# Shield_Engino.net
KiCad netlist of a schematic drawn in EAGLE
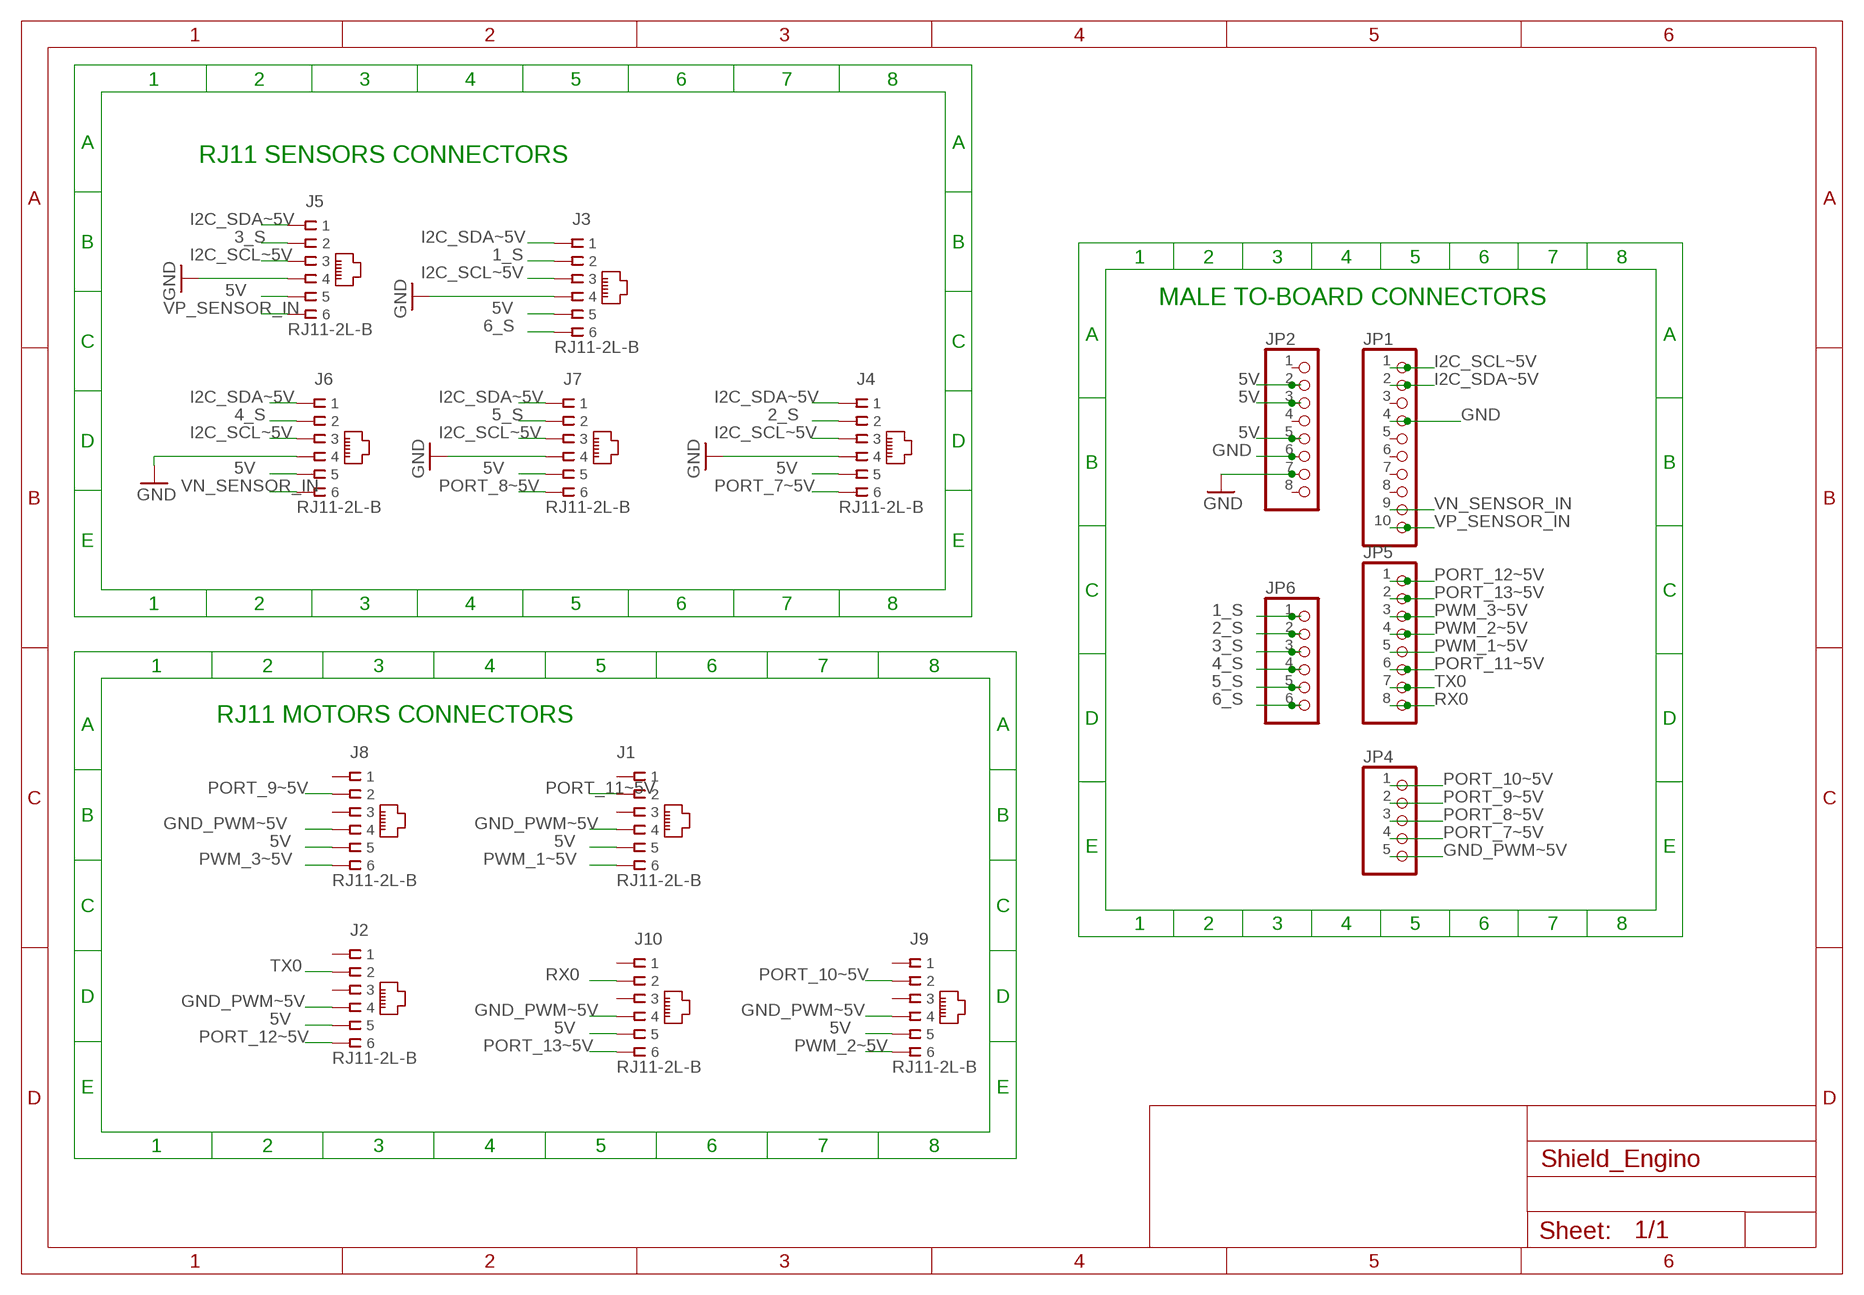
[diagram p0: schematic, sheet 1]

(export (version "E")
  (design (tool "Eeschema 10.0.6"))
  (components
    (comp (ref "J1")
      (value "RJ11-2L-B")
      (footprint "eagle-import:RJ11-NO_SHIELD")
      (fields (field (name "MF") "TYCO ELECTRONICS"))
      (libsource (lib "eagle-import") (part "RJ11-2L-B"))
    )
    (comp (ref "J2")
      (value "RJ11-2L-B")
      (footprint "eagle-import:RJ11-NO_SHIELD")
      (fields (field (name "MF") "TYCO ELECTRONICS"))
      (libsource (lib "eagle-import") (part "RJ11-2L-B"))
    )
    (comp (ref "J3")
      (value "RJ11-2L-B")
      (footprint "eagle-import:RJ11-NO_SHIELD")
      (fields (field (name "MF") "TYCO ELECTRONICS"))
      (libsource (lib "eagle-import") (part "RJ11-2L-B"))
    )
    (comp (ref "J4")
      (value "RJ11-2L-B")
      (footprint "eagle-import:RJ11-NO_SHIELD")
      (fields (field (name "MF") "TYCO ELECTRONICS"))
      (libsource (lib "eagle-import") (part "RJ11-2L-B"))
    )
    (comp (ref "J5")
      (value "RJ11-2L-B")
      (footprint "eagle-import:RJ11-NO_SHIELD")
      (fields (field (name "MF") "TYCO ELECTRONICS"))
      (libsource (lib "eagle-import") (part "RJ11-2L-B"))
    )
    (comp (ref "J6")
      (value "RJ11-2L-B")
      (footprint "eagle-import:RJ11-NO_SHIELD")
      (fields (field (name "MF") "TYCO ELECTRONICS"))
      (libsource (lib "eagle-import") (part "RJ11-2L-B"))
    )
    (comp (ref "J7")
      (value "RJ11-2L-B")
      (footprint "eagle-import:RJ11-NO_SHIELD")
      (fields (field (name "MF") "TYCO ELECTRONICS"))
      (libsource (lib "eagle-import") (part "RJ11-2L-B"))
    )
    (comp (ref "J8")
      (value "RJ11-2L-B")
      (footprint "eagle-import:RJ11-NO_SHIELD")
      (fields (field (name "MF") "TYCO ELECTRONICS"))
      (libsource (lib "eagle-import") (part "RJ11-2L-B"))
    )
    (comp (ref "J9")
      (value "RJ11-2L-B")
      (footprint "eagle-import:RJ11-NO_SHIELD")
      (fields (field (name "MF") "TYCO ELECTRONICS"))
      (libsource (lib "eagle-import") (part "RJ11-2L-B"))
    )
    (comp (ref "J10")
      (value "RJ11-2L-B")
      (footprint "eagle-import:RJ11-NO_SHIELD")
      (fields (field (name "MF") "TYCO ELECTRONICS"))
      (libsource (lib "eagle-import") (part "RJ11-2L-B"))
    )
    (comp (ref "JP1")
      (value "PINHD-1X10_2.54-SMD")
      (footprint "eagle-import:1X10SMD")
      (libsource (lib "eagle-import") (part "PINHD-1X10_2.54-SMD"))
    )
    (comp (ref "JP2")
      (value "PINHD-1X8_2.54-SMD")
      (footprint "eagle-import:1X08SMD")
      (libsource (lib "eagle-import") (part "PINHD-1X8_2.54-SMD"))
    )
    (comp (ref "JP4")
      (value "PINHD-1X5_2.54-SMD")
      (footprint "eagle-import:1X05SMD")
      (libsource (lib "eagle-import") (part "PINHD-1X5_2.54-SMD"))
    )
    (comp (ref "JP5")
      (value "PINHD-1X8_2.54-SMD")
      (footprint "eagle-import:1X08SMD")
      (libsource (lib "eagle-import") (part "PINHD-1X8_2.54-SMD"))
    )
    (comp (ref "JP6")
      (value "PINHD-1X6_2.54-SMD")
      (footprint "eagle-import:1X06SMD")
      (libsource (lib "eagle-import") (part "PINHD-1X6_2.54-SMD"))
    )
  )
  (nets
    (net (code "1") (name "/1_S") (class "Default")
      (node (ref "J3") (pin "2") (pinfunction "2_2") (pintype "passive"))
      (node (ref "JP6") (pin "1") (pinfunction "1_1") (pintype "passive"))
    )
    (net (code "2") (name "/2_S") (class "Default")
      (node (ref "J4") (pin "2") (pinfunction "2_2") (pintype "passive"))
      (node (ref "JP6") (pin "2") (pinfunction "2_2") (pintype "passive"))
    )
    (net (code "3") (name "/3_S") (class "Default")
      (node (ref "J5") (pin "2") (pinfunction "2_2") (pintype "passive"))
      (node (ref "JP6") (pin "3") (pinfunction "3_3") (pintype "passive"))
    )
    (net (code "4") (name "/4_S") (class "Default")
      (node (ref "J6") (pin "2") (pinfunction "2_2") (pintype "passive"))
      (node (ref "JP6") (pin "4") (pinfunction "4_4") (pintype "passive"))
    )
    (net (code "5") (name "/5V") (class "Default")
      (node (ref "J1") (pin "5") (pinfunction "5_5") (pintype "passive"))
      (node (ref "J10") (pin "5") (pinfunction "5_5") (pintype "passive"))
      (node (ref "J2") (pin "5") (pinfunction "5_5") (pintype "passive"))
      (node (ref "J3") (pin "5") (pinfunction "5_5") (pintype "passive"))
      (node (ref "J4") (pin "5") (pinfunction "5_5") (pintype "passive"))
      (node (ref "J5") (pin "5") (pinfunction "5_5") (pintype "passive"))
      (node (ref "J6") (pin "5") (pinfunction "5_5") (pintype "passive"))
      (node (ref "J7") (pin "5") (pinfunction "5_5") (pintype "passive"))
      (node (ref "J8") (pin "5") (pinfunction "5_5") (pintype "passive"))
      (node (ref "J9") (pin "5") (pinfunction "5_5") (pintype "passive"))
      (node (ref "JP2") (pin "2") (pinfunction "2_2") (pintype "passive"))
      (node (ref "JP2") (pin "3") (pinfunction "3_3") (pintype "passive"))
      (node (ref "JP2") (pin "5") (pinfunction "5_5") (pintype "passive"))
    )
    (net (code "6") (name "/5_S") (class "Default")
      (node (ref "J7") (pin "2") (pinfunction "2_2") (pintype "passive"))
      (node (ref "JP6") (pin "5") (pinfunction "5_5") (pintype "passive"))
    )
    (net (code "7") (name "/6_S") (class "Default")
      (node (ref "J3") (pin "6") (pinfunction "6_6") (pintype "passive"))
      (node (ref "JP6") (pin "6") (pinfunction "6_6") (pintype "passive"))
    )
    (net (code "8") (name "/GND_PWM~{5V}") (class "Default")
      (node (ref "J1") (pin "4") (pinfunction "4_4") (pintype "passive"))
      (node (ref "J10") (pin "4") (pinfunction "4_4") (pintype "passive"))
      (node (ref "J2") (pin "4") (pinfunction "4_4") (pintype "passive"))
      (node (ref "J8") (pin "4") (pinfunction "4_4") (pintype "passive"))
      (node (ref "J9") (pin "4") (pinfunction "4_4") (pintype "passive"))
      (node (ref "JP4") (pin "5") (pinfunction "5_5") (pintype "passive"))
    )
    (net (code "9") (name "/I2C_SCL~{5V}") (class "Default")
      (node (ref "J3") (pin "3") (pinfunction "3_3") (pintype "passive"))
      (node (ref "J4") (pin "3") (pinfunction "3_3") (pintype "passive"))
      (node (ref "J5") (pin "3") (pinfunction "3_3") (pintype "passive"))
      (node (ref "J6") (pin "3") (pinfunction "3_3") (pintype "passive"))
      (node (ref "J7") (pin "3") (pinfunction "3_3") (pintype "passive"))
      (node (ref "JP1") (pin "1") (pinfunction "1_1") (pintype "passive"))
    )
    (net (code "10") (name "/I2C_SDA~{5V}") (class "Default")
      (node (ref "J3") (pin "1") (pinfunction "1_1") (pintype "passive"))
      (node (ref "J4") (pin "1") (pinfunction "1_1") (pintype "passive"))
      (node (ref "J5") (pin "1") (pinfunction "1_1") (pintype "passive"))
      (node (ref "J6") (pin "1") (pinfunction "1_1") (pintype "passive"))
      (node (ref "J7") (pin "1") (pinfunction "1_1") (pintype "passive"))
      (node (ref "JP1") (pin "2") (pinfunction "2_2") (pintype "passive"))
    )
    (net (code "11") (name "/PORT_7~{5V}") (class "Default")
      (node (ref "J4") (pin "6") (pinfunction "6_6") (pintype "passive"))
      (node (ref "JP4") (pin "4") (pinfunction "4_4") (pintype "passive"))
    )
    (net (code "12") (name "/PORT_8~{5V}") (class "Default")
      (node (ref "J7") (pin "6") (pinfunction "6_6") (pintype "passive"))
      (node (ref "JP4") (pin "3") (pinfunction "3_3") (pintype "passive"))
    )
    (net (code "13") (name "/PORT_9~{5V}") (class "Default")
      (node (ref "J8") (pin "2") (pinfunction "2_2") (pintype "passive"))
      (node (ref "JP4") (pin "2") (pinfunction "2_2") (pintype "passive"))
    )
    (net (code "14") (name "/PORT_10~{5V}") (class "Default")
      (node (ref "J9") (pin "2") (pinfunction "2_2") (pintype "passive"))
      (node (ref "JP4") (pin "1") (pinfunction "1_1") (pintype "passive"))
    )
    (net (code "15") (name "/PORT_11~{5V}") (class "Default")
      (node (ref "J1") (pin "2") (pinfunction "2_2") (pintype "passive"))
      (node (ref "JP5") (pin "6") (pinfunction "6_6") (pintype "passive"))
    )
    (net (code "16") (name "/PORT_12~{5V}") (class "Default")
      (node (ref "J2") (pin "6") (pinfunction "6_6") (pintype "passive"))
      (node (ref "JP5") (pin "1") (pinfunction "1_1") (pintype "passive"))
    )
    (net (code "17") (name "/PORT_13~{5V}") (class "Default")
      (node (ref "J10") (pin "6") (pinfunction "6_6") (pintype "passive"))
      (node (ref "JP5") (pin "2") (pinfunction "2_2") (pintype "passive"))
    )
    (net (code "18") (name "/PWM_1~{5V}") (class "Default")
      (node (ref "J1") (pin "6") (pinfunction "6_6") (pintype "passive"))
      (node (ref "JP5") (pin "5") (pinfunction "5_5") (pintype "passive"))
    )
    (net (code "19") (name "/PWM_2~{5V}") (class "Default")
      (node (ref "J9") (pin "6") (pinfunction "6_6") (pintype "passive"))
      (node (ref "JP5") (pin "4") (pinfunction "4_4") (pintype "passive"))
    )
    (net (code "20") (name "/PWM_3~{5V}") (class "Default")
      (node (ref "J8") (pin "6") (pinfunction "6_6") (pintype "passive"))
      (node (ref "JP5") (pin "3") (pinfunction "3_3") (pintype "passive"))
    )
    (net (code "21") (name "/RX0") (class "Default")
      (node (ref "J10") (pin "2") (pinfunction "2_2") (pintype "passive"))
      (node (ref "JP5") (pin "8") (pinfunction "8_8") (pintype "passive"))
    )
    (net (code "22") (name "/TX0") (class "Default")
      (node (ref "J2") (pin "2") (pinfunction "2_2") (pintype "passive"))
      (node (ref "JP5") (pin "7") (pinfunction "7_7") (pintype "passive"))
    )
    (net (code "23") (name "/VN_SENSOR_IN") (class "Default")
      (node (ref "J6") (pin "6") (pinfunction "6_6") (pintype "passive"))
      (node (ref "JP1") (pin "9") (pinfunction "9_9") (pintype "passive"))
    )
    (net (code "24") (name "/VP_SENSOR_IN") (class "Default")
      (node (ref "J5") (pin "6") (pinfunction "6_6") (pintype "passive"))
      (node (ref "JP1") (pin "10") (pinfunction "10_10") (pintype "passive"))
    )
    (net (code "25") (name "GND") (class "Default")
      (node (ref "J3") (pin "4") (pinfunction "4_4") (pintype "passive"))
      (node (ref "J4") (pin "4") (pinfunction "4_4") (pintype "passive"))
      (node (ref "J5") (pin "4") (pinfunction "4_4") (pintype "passive"))
      (node (ref "J6") (pin "4") (pinfunction "4_4") (pintype "passive"))
      (node (ref "J7") (pin "4") (pinfunction "4_4") (pintype "passive"))
      (node (ref "JP1") (pin "4") (pinfunction "4_4") (pintype "passive"))
      (node (ref "JP2") (pin "6") (pinfunction "6_6") (pintype "passive"))
      (node (ref "JP2") (pin "7") (pinfunction "7_7") (pintype "passive"))
    )
    (net (code "26") (name "unconnected-(J1-Pad1)") (class "Default")
      (node (ref "J1") (pin "1") (pinfunction "1_1") (pintype "passive"))
    )
    (net (code "27") (name "unconnected-(J1-Pad3)") (class "Default")
      (node (ref "J1") (pin "3") (pinfunction "3_3") (pintype "passive"))
    )
    (net (code "28") (name "unconnected-(J2-Pad1)") (class "Default")
      (node (ref "J2") (pin "1") (pinfunction "1_1") (pintype "passive"))
    )
    (net (code "29") (name "unconnected-(J2-Pad3)") (class "Default")
      (node (ref "J2") (pin "3") (pinfunction "3_3") (pintype "passive"))
    )
    (net (code "30") (name "unconnected-(J8-Pad1)") (class "Default")
      (node (ref "J8") (pin "1") (pinfunction "1_1") (pintype "passive"))
    )
    (net (code "31") (name "unconnected-(J8-Pad3)") (class "Default")
      (node (ref "J8") (pin "3") (pinfunction "3_3") (pintype "passive"))
    )
    (net (code "32") (name "unconnected-(J9-Pad1)") (class "Default")
      (node (ref "J9") (pin "1") (pinfunction "1_1") (pintype "passive"))
    )
    (net (code "33") (name "unconnected-(J9-Pad3)") (class "Default")
      (node (ref "J9") (pin "3") (pinfunction "3_3") (pintype "passive"))
    )
    (net (code "34") (name "unconnected-(J10-Pad1)") (class "Default")
      (node (ref "J10") (pin "1") (pinfunction "1_1") (pintype "passive"))
    )
    (net (code "35") (name "unconnected-(J10-Pad3)") (class "Default")
      (node (ref "J10") (pin "3") (pinfunction "3_3") (pintype "passive"))
    )
    (net (code "36") (name "unconnected-(JP1-Pad3)") (class "Default")
      (node (ref "JP1") (pin "3") (pinfunction "3_3") (pintype "passive"))
    )
    (net (code "37") (name "unconnected-(JP1-Pad5)") (class "Default")
      (node (ref "JP1") (pin "5") (pinfunction "5_5") (pintype "passive"))
    )
    (net (code "38") (name "unconnected-(JP1-Pad6)") (class "Default")
      (node (ref "JP1") (pin "6") (pinfunction "6_6") (pintype "passive"))
    )
    (net (code "39") (name "unconnected-(JP1-Pad7)") (class "Default")
      (node (ref "JP1") (pin "7") (pinfunction "7_7") (pintype "passive"))
    )
    (net (code "40") (name "unconnected-(JP1-Pad8)") (class "Default")
      (node (ref "JP1") (pin "8") (pinfunction "8_8") (pintype "passive"))
    )
    (net (code "41") (name "unconnected-(JP2-Pad1)") (class "Default")
      (node (ref "JP2") (pin "1") (pinfunction "1_1") (pintype "passive"))
    )
    (net (code "42") (name "unconnected-(JP2-Pad4)") (class "Default")
      (node (ref "JP2") (pin "4") (pinfunction "4_4") (pintype "passive"))
    )
    (net (code "43") (name "unconnected-(JP2-Pad8)") (class "Default")
      (node (ref "JP2") (pin "8") (pinfunction "8_8") (pintype "passive"))
    )
  )
)
